# IO_Combo_SD.net
KiCad netlist of a schematic drawn in Altium Designer
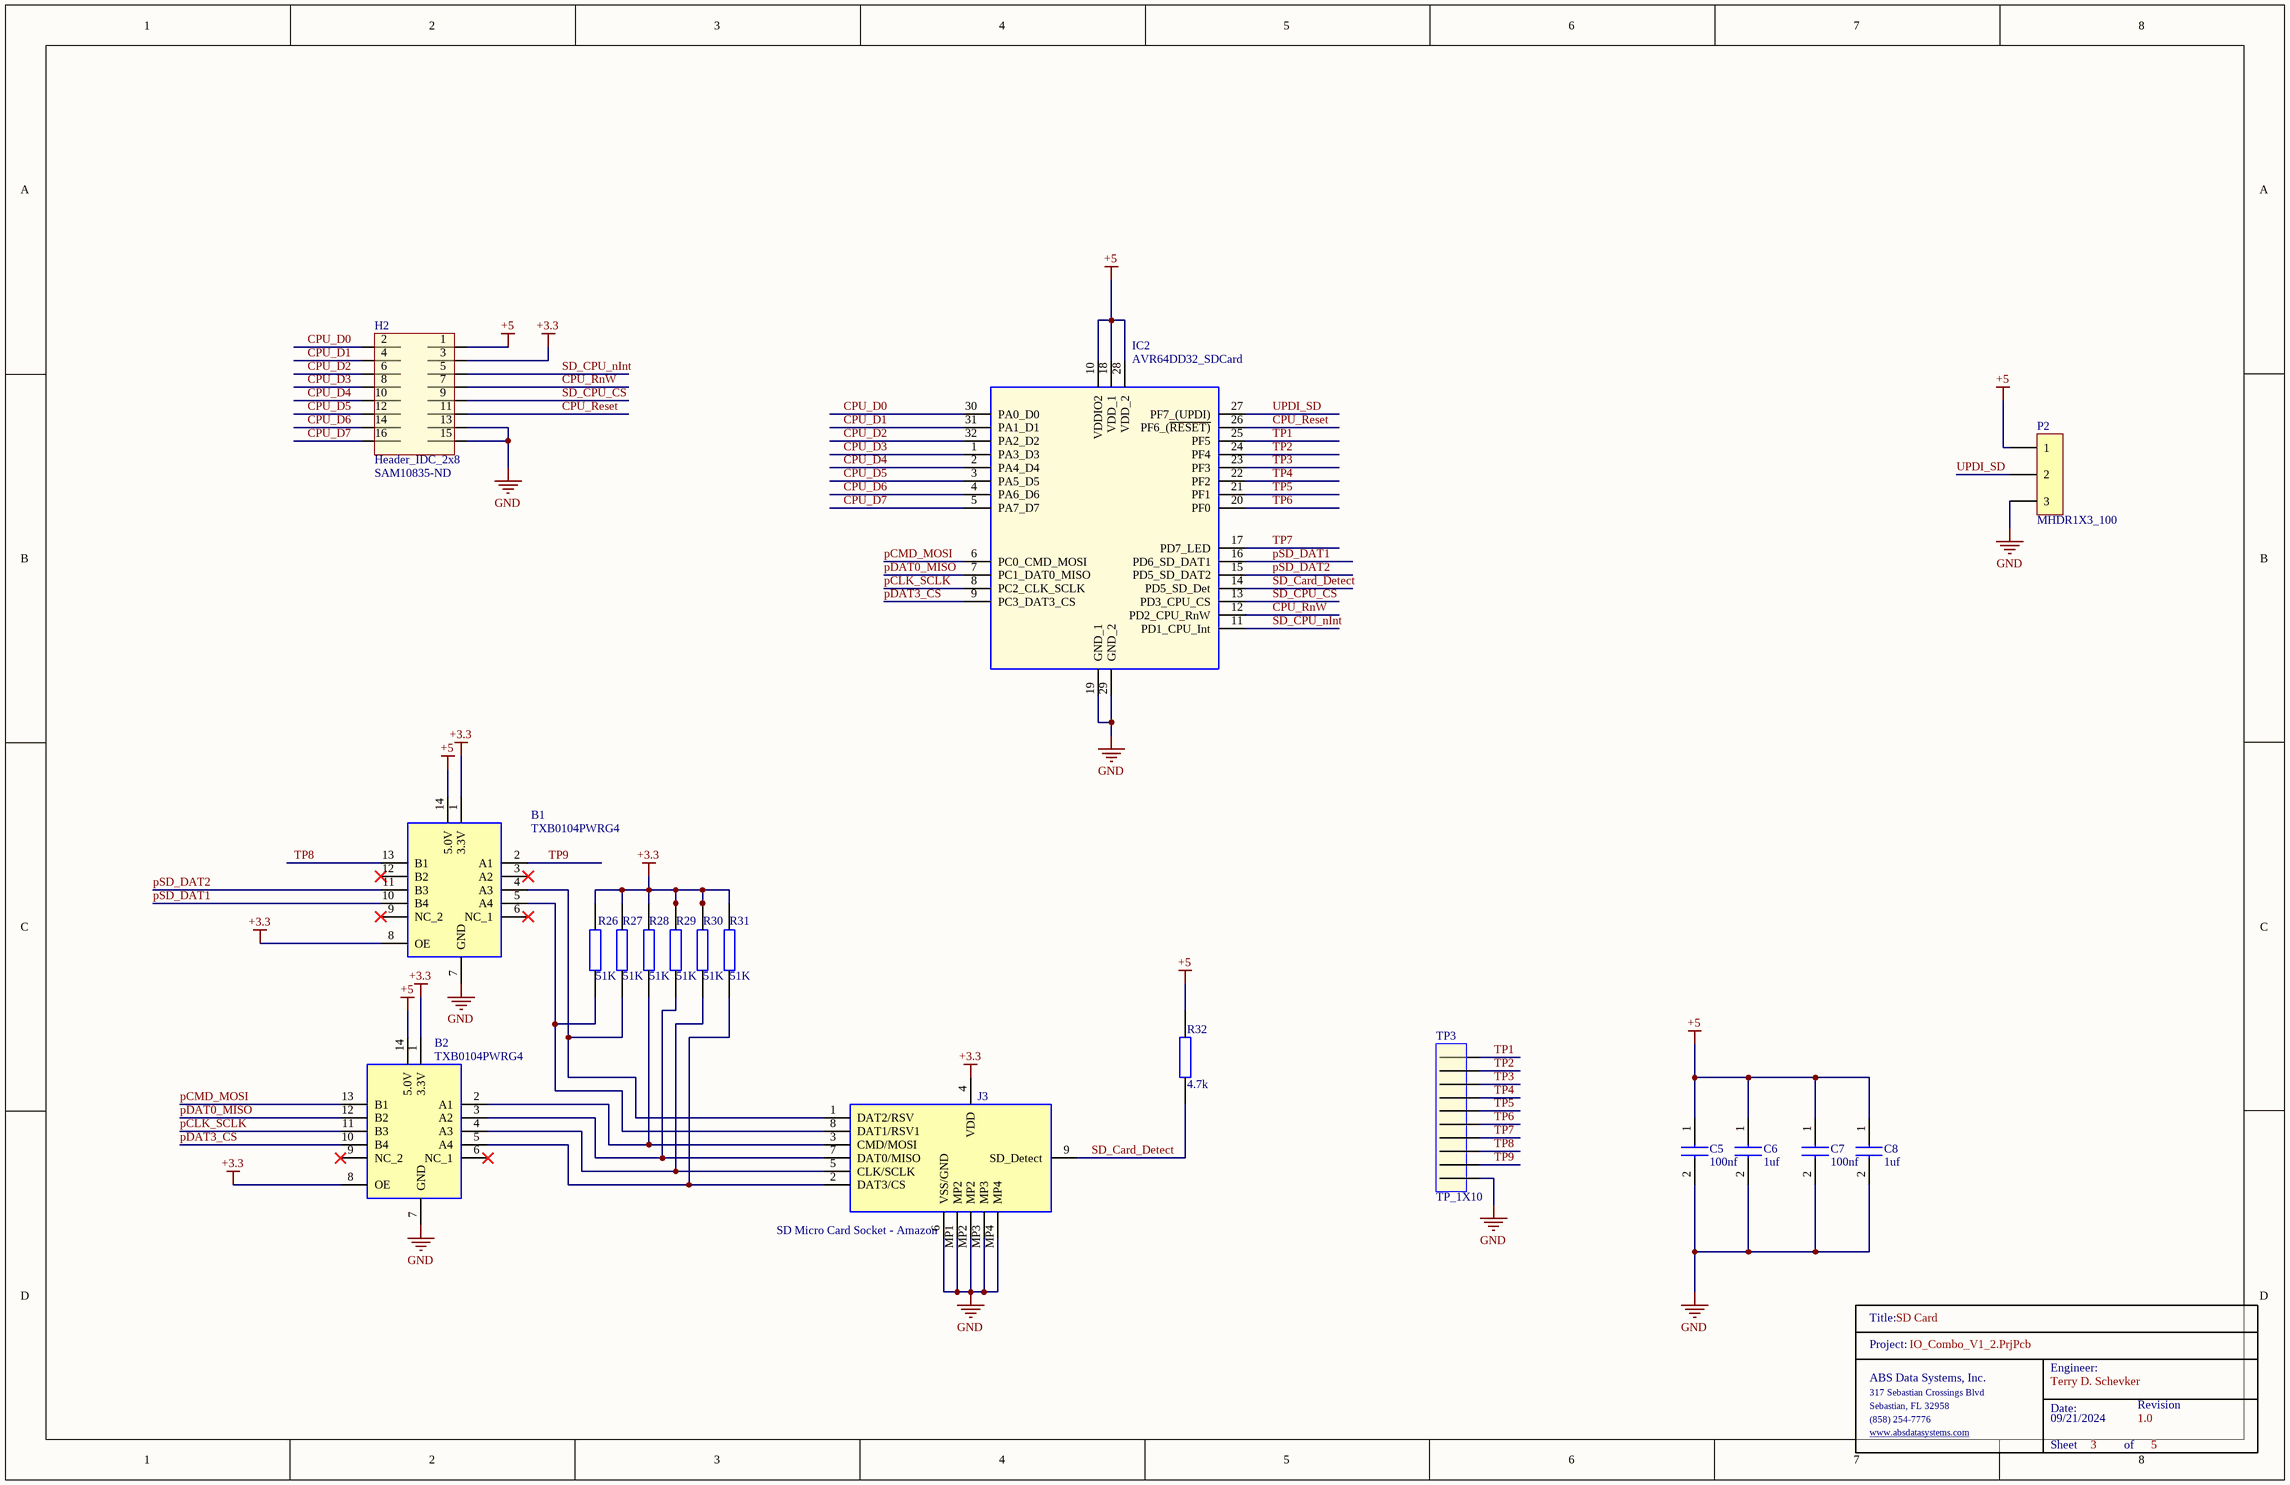
[diagram p0: IO_Combo_SD.SchDoc]

(export (version "E")
  (design (tool "Eeschema 10.0.6"))
  (components
    (comp (ref "B1")
      (value "TXB0104PWRG4")
      (footprint "SOP65P640X120-14N")
      (fields (field (name "MOUSER PART NUMBER") "595-TXB0104PWRG4"))
      (libsource (lib "Logic") (part "TXB0104PWRG4"))
    )
    (comp (ref "B2")
      (value "TXB0104PWRG4")
      (footprint "SOP65P640X120-14N")
      (fields (field (name "MOUSER PART NUMBER") "595-TXB0104PWRG4"))
      (libsource (lib "Logic") (part "TXB0104PWRG4"))
    )
    (comp (ref "C5")
      (value "100nf")
      (footprint "0603")
      (description "Samsung Electro-Mechanics 0603 100nf")
      (libsource (lib "Capacitors") (part "CL10B104JB8NNNC"))
    )
    (comp (ref "C6")
      (value "1uf")
      (footprint "0603")
      (description "Samsung Electro-Mechanics 0603 1uf")
      (libsource (lib "Capacitors") (part "CL10B105KA8NNNL"))
    )
    (comp (ref "C7")
      (value "100nf")
      (footprint "0603")
      (description "Samsung Electro-Mechanics 0603 100nf")
      (libsource (lib "Capacitors") (part "CL10B104JB8NNNC"))
    )
    (comp (ref "C8")
      (value "1uf")
      (footprint "0603")
      (description "Samsung Electro-Mechanics 0603 1uf")
      (libsource (lib "Capacitors") (part "CL10B105KA8NNNL"))
    )
    (comp (ref "H2")
      (value "Header_IDC_2x8")
      (footprint "HEADER16")
      (description "16 Pin 2x8 Through Hold IDC Connector")
      (fields
        (field (name "MANUFACTURER") "Samtec")
        (field (name "MANUFACTURER PART NUMBER") "TST-108-01-G-D")
        (field (name "SUPPLIER PART NUMBER 1") "SAM10835-ND")
      )
      (libsource (lib "Misc") (part "Header_IDC_2x8"))
    )
    (comp (ref "IC2")
      (value "AVR64DD32_SDCard")
      (footprint "QFP80P900X900X120-32N")
      (description "Integrated Circuit")
      (fields (field (name "MANUFACTURER_PART_NUMBER") "AVR64DD32-I/PT ¦ MULTI-VOLTAGE I/O"))
      (libsource (lib "CPU_Memory") (part "AVR64DD32_SDCard"))
    )
    (comp (ref "J3")
      (value "SD Micro Card Socket - Amazon")
      (footprint "SDMicroConnector")
      (description "Memory Card Connectors 9P R/A SMT MICRO SD HINGE PUSH-PULL")
      (fields
        (field (name "MOUSER PART NUMBER") "798-DM3CSSF")
        (field (name "MANUFACTURER_PART_NUMBER") "DM3CS-SF")
      )
      (libsource (lib "Connectors") (part "SD_Micro_Socket"))
    )
    (comp (ref "P2")
      (value "MHDR1X3_100")
      (footprint "MHDR1X3_100")
      (description "Header, 3-Pin")
      (fields (field (name "PUBLISHER") "Altium Limited"))
      (libsource (lib "Connectors") (part "MHDR1X3_100"))
    )
    (comp (ref "R26")
      (value "51K")
      (footprint "0603")
      (description "YAGEO 0603 51K")
      (fields
        (field (name "MOUSER PART NUMBER") "603-RC0603JR-070RL")
        (field (name "MANUFACTURER_PART_NUMBER") "RC0603JR-070RL")
      )
      (libsource (lib "Resistors") (part "RC0603FR-1051KL"))
    )
    (comp (ref "R27")
      (value "51K")
      (footprint "0603")
      (description "YAGEO 0603 51K")
      (fields
        (field (name "MOUSER PART NUMBER") "603-RC0603JR-070RL")
        (field (name "MANUFACTURER_PART_NUMBER") "RC0603JR-070RL")
      )
      (libsource (lib "Resistors") (part "RC0603FR-1051KL"))
    )
    (comp (ref "R28")
      (value "51K")
      (footprint "0603")
      (description "YAGEO 0603 51K")
      (fields
        (field (name "MOUSER PART NUMBER") "603-RC0603JR-070RL")
        (field (name "MANUFACTURER_PART_NUMBER") "RC0603JR-070RL")
      )
      (libsource (lib "Resistors") (part "RC0603FR-1051KL"))
    )
    (comp (ref "R29")
      (value "51K")
      (footprint "0603")
      (description "YAGEO 0603 51K")
      (fields
        (field (name "MOUSER PART NUMBER") "603-RC0603JR-070RL")
        (field (name "MANUFACTURER_PART_NUMBER") "RC0603JR-070RL")
      )
      (libsource (lib "Resistors") (part "RC0603FR-1051KL"))
    )
    (comp (ref "R30")
      (value "51K")
      (footprint "0603")
      (description "YAGEO 0603 51K")
      (fields
        (field (name "MOUSER PART NUMBER") "603-RC0603JR-070RL")
        (field (name "MANUFACTURER_PART_NUMBER") "RC0603JR-070RL")
      )
      (libsource (lib "Resistors") (part "RC0603FR-1051KL"))
    )
    (comp (ref "R31")
      (value "51K")
      (footprint "0603")
      (description "YAGEO 0603 51K")
      (fields
        (field (name "MOUSER PART NUMBER") "603-RC0603JR-070RL")
        (field (name "MANUFACTURER_PART_NUMBER") "RC0603JR-070RL")
      )
      (libsource (lib "Resistors") (part "RC0603FR-1051KL"))
    )
    (comp (ref "R32")
      (value "4.7k")
      (footprint "0603")
      (description "YAGEO 0603 4.7k")
      (fields
        (field (name "MOUSER PART NUMBER") "603-RC0603JR-070RL")
        (field (name "MANUFACTURER_PART_NUMBER") "RC0603JR-070RL")
      )
      (libsource (lib "Resistors") (part "RC0603FR-104K7L"))
    )
    (comp (ref "TP3")
      (value "TP_1X10")
      (footprint "TP_1X10")
      (fields
        (field (name "MANUFACTURER") "Samtec")
        (field (name "MANUFACTURER PART NUMBER") "TST-105-01-G-D")
      )
      (libsource (lib "Misc") (part "TP_1X10"))
    )
  )
  (nets
    (net (code "1") (name "+3.3") (class "Default")
      (node (ref "B1") (pin "1") (pinfunction "3.3V_1") (pintype "passive"))
      (node (ref "B1") (pin "8") (pinfunction "OE_8") (pintype "passive"))
      (node (ref "B2") (pin "1") (pinfunction "3.3V_1") (pintype "passive"))
      (node (ref "B2") (pin "8") (pinfunction "OE_8") (pintype "passive"))
      (node (ref "H2") (pin "3") (pinfunction "3_3") (pintype "passive"))
      (node (ref "J3") (pin "4") (pinfunction "VDD_4") (pintype "passive"))
      (node (ref "R26") (pin "1") (pinfunction "1_1") (pintype "passive"))
      (node (ref "R27") (pin "1") (pinfunction "1_1") (pintype "passive"))
      (node (ref "R28") (pin "1") (pinfunction "1_1") (pintype "passive"))
      (node (ref "R29") (pin "1") (pinfunction "1_1") (pintype "passive"))
      (node (ref "R30") (pin "1") (pinfunction "1_1") (pintype "passive"))
      (node (ref "R31") (pin "1") (pinfunction "1_1") (pintype "passive"))
    )
    (net (code "2") (name "+5") (class "Default")
      (node (ref "B1") (pin "14") (pinfunction "5.0V_14") (pintype "passive"))
      (node (ref "B2") (pin "14") (pinfunction "5.0V_14") (pintype "passive"))
      (node (ref "C5") (pin "1") (pinfunction "1_1") (pintype "passive"))
      (node (ref "C6") (pin "1") (pinfunction "1_1") (pintype "passive"))
      (node (ref "C7") (pin "1") (pinfunction "1_1") (pintype "passive"))
      (node (ref "C8") (pin "1") (pinfunction "1_1") (pintype "passive"))
      (node (ref "H2") (pin "1") (pinfunction "1_1") (pintype "passive"))
      (node (ref "IC2") (pin "10") (pinfunction "VDDIO2_10") (pintype "passive"))
      (node (ref "IC2") (pin "18") (pinfunction "VDD_1_18") (pintype "passive"))
      (node (ref "IC2") (pin "28") (pinfunction "VDD_2_28") (pintype "passive"))
      (node (ref "P2") (pin "1") (pinfunction "1_1") (pintype "passive"))
      (node (ref "R32") (pin "2") (pinfunction "2_2") (pintype "passive"))
    )
    (net (code "3") (name "/CPU_D0") (class "Default")
      (node (ref "H2") (pin "2") (pinfunction "2_2") (pintype "passive"))
      (node (ref "IC2") (pin "30") (pinfunction "PA0_D0_30") (pintype "passive"))
    )
    (net (code "4") (name "/CPU_D1") (class "Default")
      (node (ref "H2") (pin "4") (pinfunction "4_4") (pintype "passive"))
      (node (ref "IC2") (pin "31") (pinfunction "PA1_D1_31") (pintype "passive"))
    )
    (net (code "5") (name "/CPU_D2") (class "Default")
      (node (ref "H2") (pin "6") (pinfunction "6_6") (pintype "passive"))
      (node (ref "IC2") (pin "32") (pinfunction "PA2_D2_32") (pintype "passive"))
    )
    (net (code "6") (name "/CPU_D3") (class "Default")
      (node (ref "H2") (pin "8") (pinfunction "8_8") (pintype "passive"))
      (node (ref "IC2") (pin "1") (pinfunction "PA3_D3_1") (pintype "passive"))
    )
    (net (code "7") (name "/CPU_D4") (class "Default")
      (node (ref "H2") (pin "10") (pinfunction "10_10") (pintype "passive"))
      (node (ref "IC2") (pin "2") (pinfunction "PA4_D4_2") (pintype "passive"))
    )
    (net (code "8") (name "/CPU_D5") (class "Default")
      (node (ref "H2") (pin "12") (pinfunction "12_12") (pintype "passive"))
      (node (ref "IC2") (pin "3") (pinfunction "PA5_D5_3") (pintype "passive"))
    )
    (net (code "9") (name "/CPU_D6") (class "Default")
      (node (ref "H2") (pin "14") (pinfunction "14_14") (pintype "passive"))
      (node (ref "IC2") (pin "4") (pinfunction "PA6_D6_4") (pintype "passive"))
    )
    (net (code "10") (name "/CPU_D7") (class "Default")
      (node (ref "H2") (pin "16") (pinfunction "16_16") (pintype "passive"))
      (node (ref "IC2") (pin "5") (pinfunction "PA7_D7_5") (pintype "passive"))
    )
    (net (code "11") (name "/CPU_Reset") (class "Default")
      (node (ref "H2") (pin "11") (pinfunction "11_11") (pintype "passive"))
      (node (ref "IC2") (pin "26") (pinfunction "PF6_(~{RESET)}_26") (pintype "passive"))
    )
    (net (code "12") (name "/CPU_RnW") (class "Default")
      (node (ref "H2") (pin "7") (pinfunction "7_7") (pintype "passive"))
      (node (ref "IC2") (pin "12") (pinfunction "PD2_CPU_RnW_12") (pintype "passive"))
    )
    (net (code "13") (name "/SD_CPU_CS") (class "Default")
      (node (ref "H2") (pin "9") (pinfunction "9_9") (pintype "passive"))
      (node (ref "IC2") (pin "13") (pinfunction "PD3_CPU_CS_13") (pintype "passive"))
    )
    (net (code "14") (name "/SD_CPU_nInt") (class "Default")
      (node (ref "H2") (pin "5") (pinfunction "5_5") (pintype "passive"))
      (node (ref "IC2") (pin "11") (pinfunction "PD1_CPU_Int_11") (pintype "passive"))
    )
    (net (code "15") (name "/SD_Card_Detect") (class "Default")
      (node (ref "IC2") (pin "14") (pinfunction "PD5_SD_Det_14") (pintype "passive"))
      (node (ref "J3") (pin "9") (pinfunction "SD_Detect_9") (pintype "passive"))
      (node (ref "R32") (pin "1") (pinfunction "1_1") (pintype "passive"))
    )
    (net (code "16") (name "/TP1") (class "Default")
      (node (ref "IC2") (pin "25") (pinfunction "PF5_25") (pintype "passive"))
      (node (ref "TP3") (pin "1") (pinfunction "1_1") (pintype "passive"))
    )
    (net (code "17") (name "/TP2") (class "Default")
      (node (ref "IC2") (pin "24") (pinfunction "PF4_24") (pintype "passive"))
      (node (ref "TP3") (pin "2") (pinfunction "2_2") (pintype "passive"))
    )
    (net (code "18") (name "/TP3") (class "Default")
      (node (ref "IC2") (pin "23") (pinfunction "PF3_23") (pintype "passive"))
      (node (ref "TP3") (pin "3") (pinfunction "3_3") (pintype "passive"))
    )
    (net (code "19") (name "/TP4") (class "Default")
      (node (ref "IC2") (pin "22") (pinfunction "PF2_22") (pintype "passive"))
      (node (ref "TP3") (pin "4") (pinfunction "4_4") (pintype "passive"))
    )
    (net (code "20") (name "/TP5") (class "Default")
      (node (ref "IC2") (pin "21") (pinfunction "PF1_21") (pintype "passive"))
      (node (ref "TP3") (pin "5") (pinfunction "5_5") (pintype "passive"))
    )
    (net (code "21") (name "/TP6") (class "Default")
      (node (ref "IC2") (pin "20") (pinfunction "PF0_20") (pintype "passive"))
      (node (ref "TP3") (pin "6") (pinfunction "6_6") (pintype "passive"))
    )
    (net (code "22") (name "/TP7") (class "Default")
      (node (ref "IC2") (pin "17") (pinfunction "PD7_LED_17") (pintype "passive"))
      (node (ref "TP3") (pin "7") (pinfunction "7_7") (pintype "passive"))
    )
    (net (code "23") (name "/TP8") (class "Default")
      (node (ref "B1") (pin "13") (pinfunction "B1_13") (pintype "passive"))
      (node (ref "TP3") (pin "8") (pinfunction "8_8") (pintype "passive"))
    )
    (net (code "24") (name "/TP9") (class "Default")
      (node (ref "B1") (pin "2") (pinfunction "A1_2") (pintype "passive"))
      (node (ref "TP3") (pin "9") (pinfunction "9_9") (pintype "passive"))
    )
    (net (code "25") (name "/UPDI_SD") (class "Default")
      (node (ref "IC2") (pin "27") (pinfunction "PF7_(UPDI)_27") (pintype "passive"))
      (node (ref "P2") (pin "2") (pinfunction "2_2") (pintype "passive"))
    )
    (net (code "26") (name "/pCLK_SCLK") (class "Default")
      (node (ref "B2") (pin "11") (pinfunction "B3_11") (pintype "passive"))
      (node (ref "IC2") (pin "8") (pinfunction "PC2_CLK_SCLK_8") (pintype "passive"))
    )
    (net (code "27") (name "/pCMD_MOSI") (class "Default")
      (node (ref "B2") (pin "13") (pinfunction "B1_13") (pintype "passive"))
      (node (ref "IC2") (pin "6") (pinfunction "PC0_CMD_MOSI_6") (pintype "passive"))
    )
    (net (code "28") (name "/pDAT0_MISO") (class "Default")
      (node (ref "B2") (pin "12") (pinfunction "B2_12") (pintype "passive"))
      (node (ref "IC2") (pin "7") (pinfunction "PC1_DAT0_MISO_7") (pintype "passive"))
    )
    (net (code "29") (name "/pDAT3_CS") (class "Default")
      (node (ref "B2") (pin "10") (pinfunction "B4_10") (pintype "passive"))
      (node (ref "IC2") (pin "9") (pinfunction "PC3_DAT3_CS_9") (pintype "passive"))
    )
    (net (code "30") (name "/pSD_DAT1") (class "Default")
      (node (ref "B1") (pin "10") (pinfunction "B4_10") (pintype "passive"))
      (node (ref "IC2") (pin "16") (pinfunction "PD6_SD_DAT1_16") (pintype "passive"))
    )
    (net (code "31") (name "/pSD_DAT2") (class "Default")
      (node (ref "B1") (pin "11") (pinfunction "B3_11") (pintype "passive"))
      (node (ref "IC2") (pin "15") (pinfunction "PD5_SD_DAT2_15") (pintype "passive"))
    )
    (net (code "32") (name "GND") (class "Default")
      (node (ref "B1") (pin "7") (pinfunction "GND_7") (pintype "passive"))
      (node (ref "B2") (pin "7") (pinfunction "GND_7") (pintype "passive"))
      (node (ref "C5") (pin "2") (pinfunction "2_2") (pintype "passive"))
      (node (ref "C6") (pin "2") (pinfunction "2_2") (pintype "passive"))
      (node (ref "C7") (pin "2") (pinfunction "2_2") (pintype "passive"))
      (node (ref "C8") (pin "2") (pinfunction "2_2") (pintype "passive"))
      (node (ref "H2") (pin "13") (pinfunction "13_13") (pintype "passive"))
      (node (ref "H2") (pin "15") (pinfunction "15_15") (pintype "passive"))
      (node (ref "IC2") (pin "19") (pinfunction "GND_1_19") (pintype "passive"))
      (node (ref "IC2") (pin "29") (pinfunction "GND_2_29") (pintype "passive"))
      (node (ref "J3") (pin "6") (pinfunction "VSS/GND_6") (pintype "passive"))
      (node (ref "J3") (pin "MP1") (pinfunction "MP2_MP1") (pintype "passive"))
      (node (ref "J3") (pin "MP2") (pinfunction "MP2_MP2") (pintype "passive"))
      (node (ref "J3") (pin "MP3") (pinfunction "MP3_MP3") (pintype "passive"))
      (node (ref "J3") (pin "MP4") (pinfunction "MP4_MP4") (pintype "passive"))
      (node (ref "P2") (pin "3") (pinfunction "3_3") (pintype "passive"))
      (node (ref "TP3") (pin "10") (pinfunction "10_10") (pintype "passive"))
    )
    (net (code "33") (name "Net-(B1-A3)") (class "Default")
      (node (ref "B1") (pin "4") (pinfunction "A3_4") (pintype "passive"))
      (node (ref "J3") (pin "1") (pinfunction "DAT2/RSV_1") (pintype "passive"))
      (node (ref "R27") (pin "2") (pinfunction "2_2") (pintype "passive"))
    )
    (net (code "34") (name "Net-(B1-A4)") (class "Default")
      (node (ref "B1") (pin "5") (pinfunction "A4_5") (pintype "passive"))
      (node (ref "J3") (pin "8") (pinfunction "DAT1/RSV1_8") (pintype "passive"))
      (node (ref "R26") (pin "2") (pinfunction "2_2") (pintype "passive"))
    )
    (net (code "35") (name "Net-(B2-A1)") (class "Default")
      (node (ref "B2") (pin "2") (pinfunction "A1_2") (pintype "passive"))
      (node (ref "J3") (pin "3") (pinfunction "CMD/MOSI_3") (pintype "passive"))
      (node (ref "R28") (pin "2") (pinfunction "2_2") (pintype "passive"))
    )
    (net (code "36") (name "Net-(B2-A2)") (class "Default")
      (node (ref "B2") (pin "3") (pinfunction "A2_3") (pintype "passive"))
      (node (ref "J3") (pin "7") (pinfunction "DAT0/MISO_7") (pintype "passive"))
      (node (ref "R29") (pin "2") (pinfunction "2_2") (pintype "passive"))
    )
    (net (code "37") (name "Net-(B2-A3)") (class "Default")
      (node (ref "B2") (pin "4") (pinfunction "A3_4") (pintype "passive"))
      (node (ref "J3") (pin "5") (pinfunction "CLK/SCLK_5") (pintype "passive"))
      (node (ref "R30") (pin "2") (pinfunction "2_2") (pintype "passive"))
    )
    (net (code "38") (name "Net-(B2-A4)") (class "Default")
      (node (ref "B2") (pin "5") (pinfunction "A4_5") (pintype "passive"))
      (node (ref "J3") (pin "2") (pinfunction "DAT3/CS_2") (pintype "passive"))
      (node (ref "R31") (pin "2") (pinfunction "2_2") (pintype "passive"))
    )
    (net (code "39") (name "unconnected-(B1-A2-Pad3)") (class "Default")
      (node (ref "B1") (pin "3") (pinfunction "A2_3") (pintype "passive+no_connect"))
    )
    (net (code "40") (name "unconnected-(B1-B2-Pad12)") (class "Default")
      (node (ref "B1") (pin "12") (pinfunction "B2_12") (pintype "passive+no_connect"))
    )
    (net (code "41") (name "unconnected-(B1-NC_1-Pad6)") (class "Default")
      (node (ref "B1") (pin "6") (pinfunction "NC_1_6") (pintype "passive+no_connect"))
    )
    (net (code "42") (name "unconnected-(B1-NC_2-Pad9)") (class "Default")
      (node (ref "B1") (pin "9") (pinfunction "NC_2_9") (pintype "passive+no_connect"))
    )
    (net (code "43") (name "unconnected-(B2-NC_1-Pad6)") (class "Default")
      (node (ref "B2") (pin "6") (pinfunction "NC_1_6") (pintype "passive+no_connect"))
    )
    (net (code "44") (name "unconnected-(B2-NC_2-Pad9)") (class "Default")
      (node (ref "B2") (pin "9") (pinfunction "NC_2_9") (pintype "passive+no_connect"))
    )
  )
)
